# Dual_ESC_6-24V_3_6A_V2_Easy_EDA.net
KiCad netlist of a schematic drawn in EasyEDA Pro
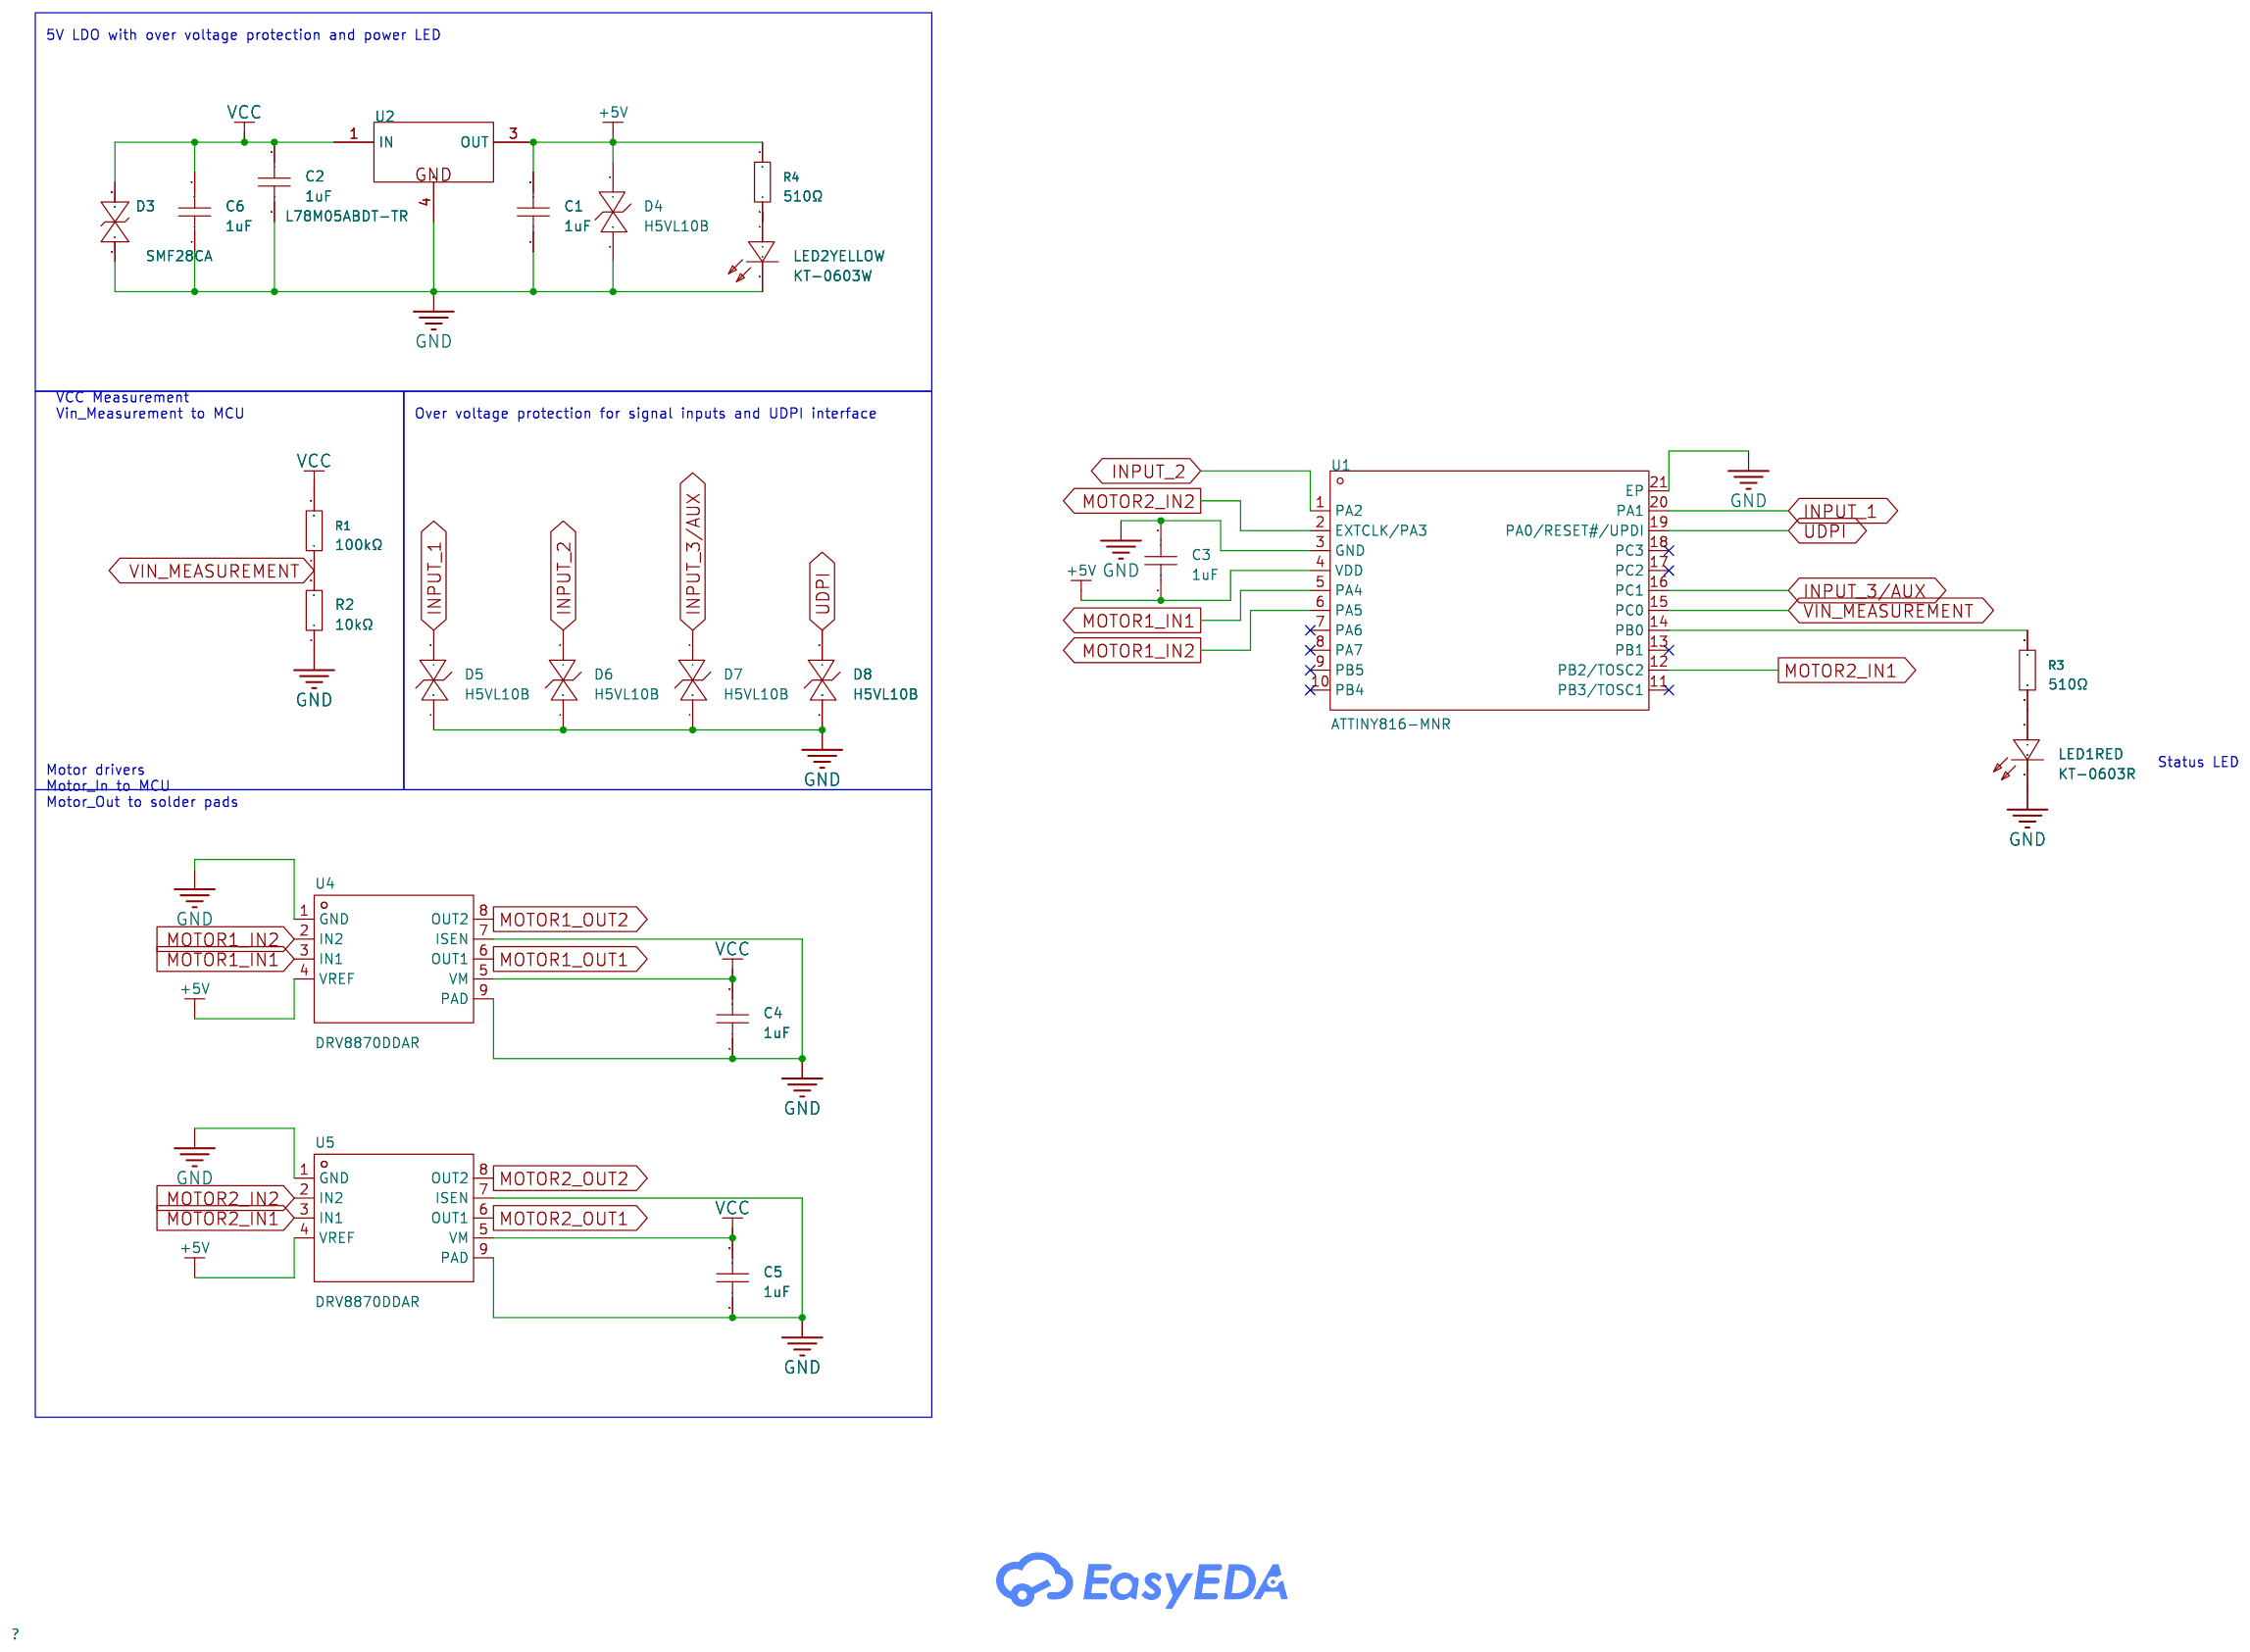
[diagram p0: schematic sheet]

(export (version "E")
  (design (tool "Eeschema 10.0.6"))
  (components
    (comp (ref "C1")
      (value "1uF")
      (footprint "easyedapro:C0402")
      (description "Capacitance:1uF Tolerance:±10% Tolerance:±10% Voltage Rating:25V Temperature Coefficient:X5R")
      (fields
        (field (name "Manufacturer Part") "CL05A105KA5NQNC")
        (field (name "Manufacturer") "SAMSUNG(三星)")
      )
      (libsource (lib "easyedapro") (part "CL05A105KA5NQNC"))
    )
    (comp (ref "C2")
      (value "1uF")
      (footprint "easyedapro:C0603")
      (description "Capacitance:1uF Tolerance:±10% Tolerance:±10% Voltage Rating:50V Temperature Coefficient:X5R")
      (fields
        (field (name "Manufacturer Part") "CL10A105KB8NNNC")
        (field (name "Manufacturer") "SAMSUNG(三星)")
      )
      (libsource (lib "easyedapro") (part "CL10A105KB8NNNC"))
    )
    (comp (ref "C3")
      (value "1uF")
      (footprint "easyedapro:C0402")
      (description "Capacitance:1uF Tolerance:±10% Tolerance:±10% Voltage Rating:25V Temperature Coefficient:X5R")
      (fields
        (field (name "Manufacturer Part") "CL05A105KA5NQNC")
        (field (name "Manufacturer") "SAMSUNG(三星)")
      )
      (libsource (lib "easyedapro") (part "CL05A105KA5NQNC"))
    )
    (comp (ref "C4")
      (value "1uF")
      (footprint "easyedapro:C0603")
      (description "Capacitance:1uF Tolerance:±10% Tolerance:±10% Voltage Rating:50V Temperature Coefficient:X5R")
      (fields
        (field (name "Manufacturer Part") "CL10A105KB8NNNC")
        (field (name "Manufacturer") "SAMSUNG(三星)")
      )
      (libsource (lib "easyedapro") (part "CL10A105KB8NNNC"))
    )
    (comp (ref "C5")
      (value "1uF")
      (footprint "easyedapro:C0603")
      (description "Capacitance:1uF Tolerance:±10% Tolerance:±10% Voltage Rating:50V Temperature Coefficient:X5R")
      (fields
        (field (name "Manufacturer Part") "CL10A105KB8NNNC")
        (field (name "Manufacturer") "SAMSUNG(三星)")
      )
      (libsource (lib "easyedapro") (part "CL10A105KB8NNNC"))
    )
    (comp (ref "C6")
      (value "1uF")
      (footprint "easyedapro:C0603")
      (description "Capacitance:1uF Tolerance:±10% Tolerance:±10% Voltage Rating:50V Temperature Coefficient:X5R")
      (fields
        (field (name "Manufacturer Part") "CL10A105KB8NNNC")
        (field (name "Manufacturer") "SAMSUNG(三星)")
      )
      (libsource (lib "easyedapro") (part "CL10A105KB8NNNC"))
    )
    (comp (ref "D3")
      (value "SMF28CA")
      (footprint "easyedapro:SOD-123FL_L2.7-W1.8-LS3.8-BI")
      (fields (field (name "Manufacturer") "R+O(宏嘉诚)"))
      (libsource (lib "easyedapro") (part "SMF28CA_C19077517"))
    )
    (comp (ref "D4")
      (value "H5VL10B")
      (footprint "easyedapro:SOD-882_L1.0-W0.6-BI")
      (fields (field (name "Manufacturer") "R+O(宏嘉诚)"))
      (libsource (lib "easyedapro") (part "H5VL10B"))
    )
    (comp (ref "D5")
      (value "H5VL10B")
      (footprint "easyedapro:SOD-882_L1.0-W0.6-BI")
      (fields (field (name "Manufacturer") "R+O(宏嘉诚)"))
      (libsource (lib "easyedapro") (part "H5VL10B"))
    )
    (comp (ref "D6")
      (value "H5VL10B")
      (footprint "easyedapro:SOD-882_L1.0-W0.6-BI")
      (fields (field (name "Manufacturer") "R+O(宏嘉诚)"))
      (libsource (lib "easyedapro") (part "H5VL10B"))
    )
    (comp (ref "D7")
      (value "H5VL10B")
      (footprint "easyedapro:SOD-882_L1.0-W0.6-BI")
      (fields (field (name "Manufacturer") "R+O(宏嘉诚)"))
      (libsource (lib "easyedapro") (part "H5VL10B"))
    )
    (comp (ref "D8")
      (value "H5VL10B")
      (footprint "easyedapro:SOD-882_L1.0-W0.6-BI")
      (fields (field (name "Manufacturer") "R+O(宏嘉诚)"))
      (libsource (lib "easyedapro") (part "H5VL10B"))
    )
    (comp (ref "LED1RED")
      (value "KT-0603R")
      (footprint "easyedapro:LED0603-RD")
      (fields (field (name "Manufacturer") "KENTO"))
      (libsource (lib "easyedapro") (part "KT-0603R"))
    )
    (comp (ref "LED2YELLOW")
      (value "KT-0603W")
      (footprint "easyedapro:LED0603-R-RD_WHITE")
      (fields (field (name "Manufacturer") "KENTO"))
      (libsource (lib "easyedapro") (part "0603White light_C2290"))
    )
    (comp (ref "R1")
      (value "100kΩ")
      (footprint "easyedapro:R0402")
      (fields
        (field (name "Manufacturer Part") "0402WGF1003TCE")
        (field (name "Manufacturer") "UNI-ROYAL(厚声)")
      )
      (libsource (lib "easyedapro") (part "0402WGF1003TCE"))
    )
    (comp (ref "R2")
      (value "10kΩ")
      (footprint "easyedapro:R0402")
      (fields
        (field (name "Manufacturer Part") "0402WGF1002TCE")
        (field (name "Manufacturer") "UNI-ROYAL(厚声)")
      )
      (libsource (lib "easyedapro") (part "0402WGF1002TCE"))
    )
    (comp (ref "R3")
      (value "510Ω")
      (footprint "easyedapro:R0402")
      (fields
        (field (name "Manufacturer Part") "0402WGF5100TCE")
        (field (name "Manufacturer") "UNI-ROYAL(厚声)")
      )
      (libsource (lib "easyedapro") (part "0402WGF5100TCE"))
    )
    (comp (ref "R4")
      (value "510Ω")
      (footprint "easyedapro:R0402")
      (fields
        (field (name "Manufacturer Part") "0402WGF5100TCE")
        (field (name "Manufacturer") "UNI-ROYAL(厚声)")
      )
      (libsource (lib "easyedapro") (part "0402WGF5100TCE"))
    )
    (comp (ref "U1")
      (value "ATTINY816-MNR")
      (fields (field (name "Manufacturer") "MICROCHIP(美国微芯)"))
      (libsource (lib "easyedapro") (part "ATTINY1616-MNR"))
    )
    (comp (ref "U2")
      (value "L78M05ABDT-TR")
      (footprint "easyedapro:TO-252-2_L6.5-W6.1-P4.58-LS10.0-TL")
      (fields (field (name "Manufacturer") "ST(意法半导体)"))
      (libsource (lib "easyedapro") (part "L78M05ABDT-TR"))
    )
    (comp (ref "U4")
      (value "DRV8870DDAR")
      (footprint "easyedapro:HSOP-8_L5.0-W4.0-P1.27-LS6.2-BL-EP")
      (fields (field (name "Manufacturer") "TI(德州仪器)"))
      (libsource (lib "easyedapro") (part "DRV8870DDAR"))
    )
    (comp (ref "U5")
      (value "DRV8870DDAR")
      (footprint "easyedapro:HSOP-8_L5.0-W4.0-P1.27-LS6.2-BL-EP")
      (fields (field (name "Manufacturer") "TI(德州仪器)"))
      (libsource (lib "easyedapro") (part "DRV8870DDAR"))
    )
  )
  (nets
    (net (code "1") (name "+5V") (class "Default")
      (node (ref "C1") (pin "2") (pinfunction "2_2") (pintype "unspecified"))
      (node (ref "C3") (pin "1") (pinfunction "1_1") (pintype "unspecified"))
      (node (ref "D4") (pin "2") (pinfunction "A_2") (pintype "unspecified"))
      (node (ref "R4") (pin "2") (pinfunction "2_2") (pintype "input"))
      (node (ref "U1") (pin "4") (pinfunction "VDD_4") (pintype "unspecified"))
      (node (ref "U2") (pin "3") (pinfunction "OUT_3") (pintype "unspecified"))
      (node (ref "U4") (pin "4") (pinfunction "VREF_4") (pintype "unspecified"))
      (node (ref "U5") (pin "4") (pinfunction "VREF_4") (pintype "unspecified"))
    )
    (net (code "2") (name "GND") (class "Default")
      (node (ref "C1") (pin "1") (pinfunction "1_1") (pintype "unspecified"))
      (node (ref "C2") (pin "1") (pinfunction "1_1") (pintype "unspecified"))
      (node (ref "C3") (pin "2") (pinfunction "2_2") (pintype "unspecified"))
      (node (ref "C4") (pin "1") (pinfunction "1_1") (pintype "unspecified"))
      (node (ref "C5") (pin "1") (pinfunction "1_1") (pintype "unspecified"))
      (node (ref "C6") (pin "1") (pinfunction "1_1") (pintype "unspecified"))
      (node (ref "D3") (pin "1") (pinfunction "1_1") (pintype "unspecified"))
      (node (ref "D4") (pin "1") (pinfunction "C_1") (pintype "unspecified"))
      (node (ref "D5") (pin "1") (pinfunction "C_1") (pintype "unspecified"))
      (node (ref "D6") (pin "1") (pinfunction "C_1") (pintype "unspecified"))
      (node (ref "D7") (pin "1") (pinfunction "C_1") (pintype "unspecified"))
      (node (ref "D8") (pin "1") (pinfunction "C_1") (pintype "unspecified"))
      (node (ref "LED1RED") (pin "1") (pinfunction "K_1") (pintype "unspecified"))
      (node (ref "LED2YELLOW") (pin "2") (pinfunction "K_2") (pintype "unspecified"))
      (node (ref "R2") (pin "1") (pinfunction "1_1") (pintype "input"))
      (node (ref "U1") (pin "21") (pinfunction "EP_21") (pintype "unspecified"))
      (node (ref "U1") (pin "3") (pinfunction "GND_3") (pintype "unspecified"))
      (node (ref "U2") (pin "4") (pinfunction "GND_4") (pintype "unspecified"))
      (node (ref "U4") (pin "1") (pinfunction "GND_1") (pintype "unspecified"))
      (node (ref "U4") (pin "7") (pinfunction "ISEN_7") (pintype "unspecified"))
      (node (ref "U4") (pin "9") (pinfunction "PAD_9") (pintype "unspecified"))
      (node (ref "U5") (pin "1") (pinfunction "GND_1") (pintype "unspecified"))
      (node (ref "U5") (pin "7") (pinfunction "ISEN_7") (pintype "unspecified"))
      (node (ref "U5") (pin "9") (pinfunction "PAD_9") (pintype "unspecified"))
    )
    (net (code "3") (name "INPUT_1") (class "Default")
      (node (ref "D5") (pin "2") (pinfunction "A_2") (pintype "unspecified"))
      (node (ref "U1") (pin "20") (pinfunction "PA1_20") (pintype "unspecified"))
    )
    (net (code "4") (name "INPUT_2") (class "Default")
      (node (ref "D6") (pin "2") (pinfunction "A_2") (pintype "unspecified"))
      (node (ref "U1") (pin "1") (pinfunction "PA2_1") (pintype "unspecified"))
    )
    (net (code "5") (name "INPUT_3{slash}AUX") (class "Default")
      (node (ref "D7") (pin "2") (pinfunction "A_2") (pintype "unspecified"))
      (node (ref "U1") (pin "16") (pinfunction "PC1_16") (pintype "unspecified"))
    )
    (net (code "6") (name "MOTOR1_IN1") (class "Default")
      (node (ref "U1") (pin "5") (pinfunction "PA4_5") (pintype "unspecified"))
      (node (ref "U4") (pin "3") (pinfunction "IN1_3") (pintype "unspecified"))
    )
    (net (code "7") (name "MOTOR1_IN2") (class "Default")
      (node (ref "U1") (pin "6") (pinfunction "PA5_6") (pintype "unspecified"))
      (node (ref "U4") (pin "2") (pinfunction "IN2_2") (pintype "unspecified"))
    )
    (net (code "8") (name "MOTOR1_OUT1") (class "Default")
      (node (ref "U4") (pin "6") (pinfunction "OUT1_6") (pintype "unspecified"))
    )
    (net (code "9") (name "MOTOR1_OUT2") (class "Default")
      (node (ref "U4") (pin "8") (pinfunction "OUT2_8") (pintype "unspecified"))
    )
    (net (code "10") (name "MOTOR2_IN1") (class "Default")
      (node (ref "U1") (pin "12") (pinfunction "PB2/TOSC2_12") (pintype "unspecified"))
      (node (ref "U5") (pin "3") (pinfunction "IN1_3") (pintype "unspecified"))
    )
    (net (code "11") (name "MOTOR2_IN2") (class "Default")
      (node (ref "U1") (pin "2") (pinfunction "EXTCLK/PA3_2") (pintype "unspecified"))
      (node (ref "U5") (pin "2") (pinfunction "IN2_2") (pintype "unspecified"))
    )
    (net (code "12") (name "MOTOR2_OUT1") (class "Default")
      (node (ref "U5") (pin "6") (pinfunction "OUT1_6") (pintype "unspecified"))
    )
    (net (code "13") (name "MOTOR2_OUT2") (class "Default")
      (node (ref "U5") (pin "8") (pinfunction "OUT2_8") (pintype "unspecified"))
    )
    (net (code "14") (name "Net-(LED1RED-A)") (class "Default")
      (node (ref "LED1RED") (pin "2") (pinfunction "A_2") (pintype "unspecified"))
      (node (ref "R3") (pin "1") (pinfunction "1_1") (pintype "input"))
    )
    (net (code "15") (name "Net-(LED2YELLOW-A)") (class "Default")
      (node (ref "LED2YELLOW") (pin "1") (pinfunction "A_1") (pintype "unspecified"))
      (node (ref "R4") (pin "1") (pinfunction "1_1") (pintype "input"))
    )
    (net (code "16") (name "Net-(U1-PB0)") (class "Default")
      (node (ref "R3") (pin "2") (pinfunction "2_2") (pintype "input"))
      (node (ref "U1") (pin "14") (pinfunction "PB0_14") (pintype "unspecified"))
    )
    (net (code "17") (name "UDPI") (class "Default")
      (node (ref "D8") (pin "2") (pinfunction "A_2") (pintype "unspecified"))
      (node (ref "U1") (pin "19") (pinfunction "PA0/RESET#/UPDI_19") (pintype "unspecified"))
    )
    (net (code "18") (name "VCC") (class "Default")
      (node (ref "C2") (pin "2") (pinfunction "2_2") (pintype "unspecified"))
      (node (ref "C4") (pin "2") (pinfunction "2_2") (pintype "unspecified"))
      (node (ref "C5") (pin "2") (pinfunction "2_2") (pintype "unspecified"))
      (node (ref "C6") (pin "2") (pinfunction "2_2") (pintype "unspecified"))
      (node (ref "D3") (pin "2") (pinfunction "2_2") (pintype "unspecified"))
      (node (ref "R1") (pin "2") (pinfunction "2_2") (pintype "input"))
      (node (ref "U2") (pin "1") (pinfunction "IN_1") (pintype "unspecified"))
      (node (ref "U4") (pin "5") (pinfunction "VM_5") (pintype "unspecified"))
      (node (ref "U5") (pin "5") (pinfunction "VM_5") (pintype "unspecified"))
    )
    (net (code "19") (name "VIN_MEASUREMENT") (class "Default")
      (node (ref "R1") (pin "1") (pinfunction "1_1") (pintype "input"))
      (node (ref "R2") (pin "2") (pinfunction "2_2") (pintype "input"))
      (node (ref "U1") (pin "15") (pinfunction "PC0_15") (pintype "unspecified"))
    )
    (net (code "20") (name "unconnected-(U1-PA6-Pad7)") (class "Default")
      (node (ref "U1") (pin "7") (pinfunction "PA6_7") (pintype "unspecified+no_connect"))
    )
    (net (code "21") (name "unconnected-(U1-PA7-Pad8)") (class "Default")
      (node (ref "U1") (pin "8") (pinfunction "PA7_8") (pintype "unspecified+no_connect"))
    )
    (net (code "22") (name "unconnected-(U1-PB1-Pad13)") (class "Default")
      (node (ref "U1") (pin "13") (pinfunction "PB1_13") (pintype "unspecified+no_connect"))
    )
    (net (code "23") (name "unconnected-(U1-PB3{slash}TOSC1-Pad11)") (class "Default")
      (node (ref "U1") (pin "11") (pinfunction "PB3/TOSC1_11") (pintype "unspecified+no_connect"))
    )
    (net (code "24") (name "unconnected-(U1-PB4-Pad10)") (class "Default")
      (node (ref "U1") (pin "10") (pinfunction "PB4_10") (pintype "unspecified+no_connect"))
    )
    (net (code "25") (name "unconnected-(U1-PB5-Pad9)") (class "Default")
      (node (ref "U1") (pin "9") (pinfunction "PB5_9") (pintype "unspecified+no_connect"))
    )
    (net (code "26") (name "unconnected-(U1-PC2-Pad17)") (class "Default")
      (node (ref "U1") (pin "17") (pinfunction "PC2_17") (pintype "unspecified+no_connect"))
    )
    (net (code "27") (name "unconnected-(U1-PC3-Pad18)") (class "Default")
      (node (ref "U1") (pin "18") (pinfunction "PC3_18") (pintype "unspecified+no_connect"))
    )
  )
)
